# Buck_converter.net
KiCad netlist of a schematic drawn in Altium Designer
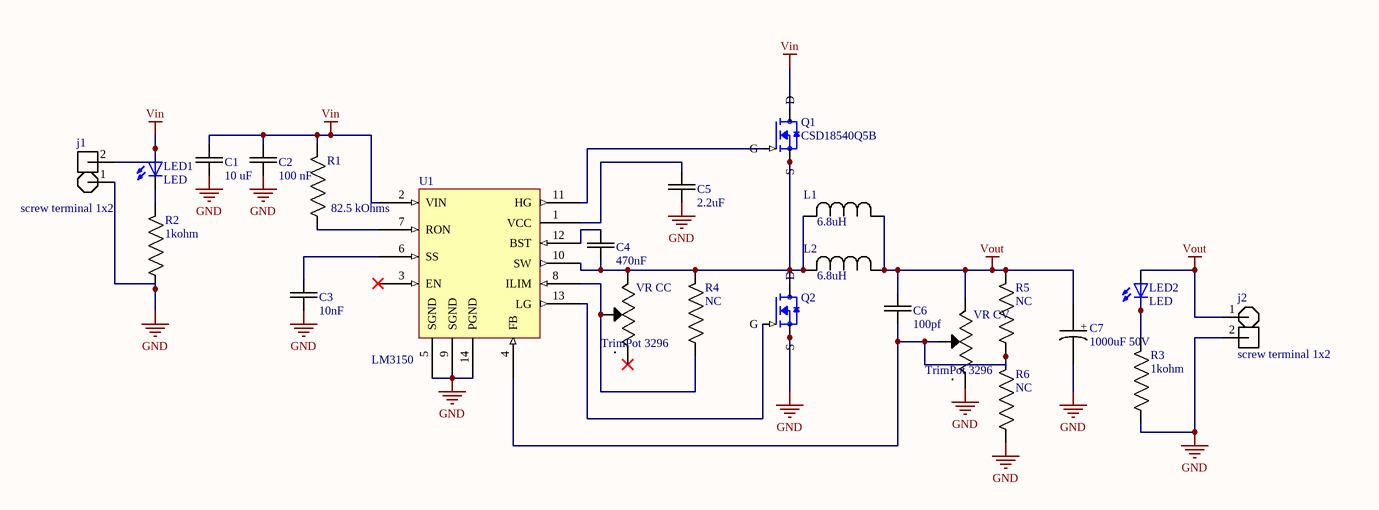
[diagram p0: Buck converter.SchDoc]

(export (version "E")
  (design (tool "Eeschema 10.0.6"))
  (components
    (comp (ref "C1")
      (value "10 uF")
      (footprint "SMD Cap 805")
      (description "0805 10 uF 50 V ±20% Tolerance X5R Multilayer Ceramic Capacitor")
      (fields
        (field (name "MANUFACTURER") "Murata")
        (field (name "MANUFACTURER PART NUMBER") "GRM21BR6YA106ME43L")
      )
      (libsource (lib "Integrated_Library") (part "Cap SMD"))
    )
    (comp (ref "C2")
      (value "100 nF")
      (footprint "SMD Cap 805")
      (fields
        (field (name "MANUFACTURER") "Kyocera AVX")
        (field (name "MANUFACTURER PART NUMBER") "08055C104KAT2A")
        (field (name "TOLERANCE") "10%")
      )
      (libsource (lib "Integrated_Library") (part "Cap SMD"))
    )
    (comp (ref "C3")
      (value "10nF")
      (footprint "SMD Cap 805")
      (description "Capacitor 10 nF 50 VDC PU=4000 ST, C0805C103K5RACTU, KEMET")
      (fields
        (field (name "MANUFACTURER") "KEMET")
        (field (name "MANUFACTURER PART NUMBER") "C0805C103K5RAC-TU")
      )
      (libsource (lib "Integrated_Library") (part "Cap SMD"))
    )
    (comp (ref "C4")
      (value "470nF")
      (footprint "SMD Cap 805")
      (fields
        (field (name "MANUFACTURER") "Taiyo Yuden")
        (field (name "MANUFACTURER PART NUMBER") "GMK212BJ474KG-T")
        (field (name "TOLERANCE") "10%")
      )
      (libsource (lib "Integrated_Library") (part "Cap SMD"))
    )
    (comp (ref "C5")
      (value "2.2uF")
      (footprint "SMD Cap 805")
      (description "CAP CER 2.2UF 35V X6S 0805")
      (fields
        (field (name "MANUFACTURER") "TDK")
        (field (name "MANUFACTURER PART NUMBER") "C2012X6S1V225K125AB")
      )
      (libsource (lib "Integrated_Library") (part "Cap SMD"))
    )
    (comp (ref "C6")
      (value "100pf")
      (footprint "SMD Cap 805")
      (fields
        (field (name "MANUFACTURER") "KEMET")
        (field (name "MANUFACTURER PART NUMBER") "C0805C101J1GACTU")
        (field (name "TOLERANCE") "5%")
      )
      (libsource (lib "Integrated_Library") (part "Cap SMD"))
    )
    (comp (ref "C7")
      (value "1000uF 50V")
      (footprint "CAP ELECTROLYTE 1000UF 50V")
      (description "CAP ALUM 1000UF 20% 50V RADIAL")
      (fields
        (field (name "MANUFACTURER") "United Chemi-Con")
        (field (name "MANUFACTURER PART NUMBER") "EKMG500ETC1R0ME11D")
      )
      (libsource (lib "Integrated_Library") (part "Cap electrolyte"))
    )
    (comp (ref "j1")
      (value "screw terminal 1x2")
      (footprint "screw terminal 1x2")
      (fields
        (field (name "MANUFACTURER") "Wurth Electronics")
        (field (name "MANUFACTURER PART NUMBER") "691214110002")
        (field (name "VOLTAGE") "300V")
      )
      (libsource (lib "connectors") (part "screw terminal 1x2"))
    )
    (comp (ref "j2")
      (value "screw terminal 1x2")
      (footprint "screw terminal 1x2")
      (fields
        (field (name "MANUFACTURER") "Wurth Electronics")
        (field (name "MANUFACTURER PART NUMBER") "691214110002")
        (field (name "VOLTAGE") "300V")
      )
      (libsource (lib "connectors") (part "screw terminal 1x2"))
    )
    (comp (ref "L1")
      (value "6.8uH")
      (footprint "Inductor DR127")
      (description "General Purpose Inductor, 6.8uH, 20%, 1 Element, Ferrite-Core, SMD, 4949")
      (fields
        (field (name "MANUFACTURER") "Eaton Cooper")
        (field (name "MANUFACTURER PART NUMBER") "DR127-470-R")
      )
      (libsource (lib "Integrated_Library") (part "Inductor CDRH127"))
    )
    (comp (ref "L2")
      (value "6.8uH")
      (footprint "Inductor DR127")
      (description "General Purpose Inductor, 6.8uH, 20%, 1 Element, Ferrite-Core, SMD, 4949")
      (fields
        (field (name "MANUFACTURER") "Eaton Cooper")
        (field (name "MANUFACTURER PART NUMBER") "DR127-470-R")
      )
      (libsource (lib "Integrated_Library") (part "Inductor CDRH127"))
    )
    (comp (ref "LED1")
      (value "LED")
      (footprint "LED3MM")
      (description "LED 3 mm (T1) red, 151031SS04000, Würth Elektronik")
      (fields
        (field (name "MANUFACTURER") "Wurth Electronics")
        (field (name "MANUFACTURER PART NUMBER") "151031SS04000")
      )
      (libsource (lib "Integrated_Library") (part "LED"))
    )
    (comp (ref "LED2")
      (value "LED")
      (footprint "LED3MM")
      (description "LED 3 mm (T1) red, 151031SS04000, Würth Elektronik")
      (fields
        (field (name "MANUFACTURER") "Wurth Electronics")
        (field (name "MANUFACTURER PART NUMBER") "151031SS04000")
      )
      (libsource (lib "Integrated_Library") (part "LED"))
    )
    (comp (ref "Q1")
      (value "CSD18540Q5B")
      (footprint "VSON-CLIP-8 - V2")
      (description "N-Channel 60V 100A _Ta_ 3.1W _Ta_, 195W _Tc_ Surface Mount 8-VSON-CLIP _5x6_")
      (fields (field (name "MF") "Texas Instruments") (field (name "DIGI-KEY_PART_NUMBER") "296-41076-1-ND"))
      (libsource (lib "Integrated_Library") (part "CSD18540Q5B"))
    )
    (comp (ref "Q2")
      (value "CSD18540Q5B")
      (footprint "VSON-CLIP-8 - V2")
      (description "N-Channel 60V 100A _Ta_ 3.1W _Ta_, 195W _Tc_ Surface Mount 8-VSON-CLIP _5x6_")
      (fields (field (name "MF") "Texas Instruments") (field (name "DIGI-KEY_PART_NUMBER") "296-41076-1-ND"))
      (libsource (lib "Integrated_Library") (part "CSD18540Q5B"))
    )
    (comp (ref "R1")
      (value "82.5 kOhms")
      (footprint "SMD Resistor 805")
      (fields
        (field (name "MANUFACTURER") "Panasonic")
        (field (name "MANUFACTURER PART NUMBER") "ERJ-6ENF8252V")
        (field (name "TOLERANCE") "1%")
      )
      (libsource (lib "Integrated_Library") (part "Resistor SMD"))
    )
    (comp (ref "R2")
      (value "1kohm")
      (footprint "SMD Resistor 805")
      (fields
        (field (name "MANUFACTURER") "Yageo")
        (field (name "MANUFACTURER PART NUMBER") "RC0805FR-071KL")
        (field (name "TOLERANCE") "1%")
      )
      (libsource (lib "Integrated_Library") (part "Resistor SMD"))
    )
    (comp (ref "R3")
      (value "1kohm")
      (footprint "SMD Resistor 805")
      (fields
        (field (name "MANUFACTURER") "Yageo")
        (field (name "MANUFACTURER PART NUMBER") "RC0805FR-071KL")
        (field (name "TOLERANCE") "1%")
      )
      (libsource (lib "Integrated_Library") (part "Resistor SMD"))
    )
    (comp (ref "R4")
      (value "NC")
      (footprint "SMD Resistor 805")
      (fields
        (field (name "MANUFACTURER") "Yageo")
        (field (name "MANUFACTURER PART NUMBER") "RC0805FR-071KL")
        (field (name "TOLERANCE") "1%")
      )
      (libsource (lib "Integrated_Library") (part "Resistor SMD"))
    )
    (comp (ref "R5")
      (value "NC")
      (footprint "SMD Resistor 805")
      (fields
        (field (name "MANUFACTURER") "Yageo")
        (field (name "MANUFACTURER PART NUMBER") "RC0805FR-071KL")
        (field (name "TOLERANCE") "1%")
      )
      (libsource (lib "Integrated_Library") (part "Resistor SMD"))
    )
    (comp (ref "R6")
      (value "NC")
      (footprint "SMD Resistor 805")
      (libsource (lib "Integrated_Library") (part "Resistor SMD"))
    )
    (comp (ref "U1")
      (value "LM3150")
      (footprint "HTSSOP (14)")
      (description "IC REG CTRLR BUCK 14TSSOP")
      (fields
        (field (name "MANUFACTURER") "TI National Semiconductor")
        (field (name "MANUFACTURER PART NUMBER") "LM3150MHX/NOPB")
      )
      (libsource (lib "Integrated_Library") (part "LM3150"))
    )
    (comp (ref "VR CC")
      (value "TrimPot 3296")
      (footprint "TrimPOT 3296W")
      (description "Trimmer Resistors - Through Hole 3/8 1Kohms Sealed Vertical Adjust")
      (fields
        (field (name "MANUFACTURER") "Bourns")
        (field (name "MANUFACTURER PART NUMBER") "3296W-1-102LF")
      )
      (libsource (lib "Integrated_Library") (part "TrimPot 3296W"))
    )
    (comp (ref "VR CV")
      (value "TrimPot 3296")
      (footprint "TrimPOT 3296W")
      (description "Trimmer Resistors - Through Hole 3/8 1Kohms Sealed Vertical Adjust")
      (fields
        (field (name "MANUFACTURER") "Bourns")
        (field (name "MANUFACTURER PART NUMBER") "3296W-1-102LF")
      )
      (libsource (lib "Integrated_Library") (part "TrimPot 3296W"))
    )
  )
  (nets
    (net (code "1") (name "GND") (class "Default")
      (node (ref "C1") (pin "1") (pintype "passive"))
      (node (ref "C2") (pin "1") (pintype "passive"))
      (node (ref "C3") (pin "1") (pintype "passive"))
      (node (ref "C5") (pin "1") (pintype "passive"))
      (node (ref "C7") (pin "N") (pinfunction "-_N") (pintype "passive"))
      (node (ref "Q2") (pin "1") (pinfunction "S_1") (pintype "power_in"))
      (node (ref "Q2") (pin "2") (pinfunction "S_2") (pintype "power_in"))
      (node (ref "Q2") (pin "3") (pinfunction "S_3") (pintype "power_in"))
      (node (ref "R2") (pin "1") (pinfunction "1_1") (pintype "passive"))
      (node (ref "R3") (pin "1") (pinfunction "1_1") (pintype "passive"))
      (node (ref "R6") (pin "1") (pinfunction "1_1") (pintype "passive"))
      (node (ref "U1") (pin "14") (pinfunction "PGND_14") (pintype "power_in"))
      (node (ref "U1") (pin "5") (pinfunction "SGND_5") (pintype "passive"))
      (node (ref "U1") (pin "9") (pinfunction "SGND_9") (pintype "passive"))
      (node (ref "VR CV") (pin "1") (pinfunction "CCW_1") (pintype "passive"))
      (node (ref "j1") (pin "1") (pinfunction "1_1") (pintype "passive"))
      (node (ref "j2") (pin "2") (pinfunction "2_2") (pintype "passive"))
    )
    (net (code "2") (name "Net-(LED1-PadC)") (class "Default")
      (node (ref "LED1") (pin "C") (pinfunction "C_C") (pintype "passive"))
      (node (ref "R2") (pin "2") (pinfunction "2_2") (pintype "passive"))
    )
    (net (code "3") (name "Net-(LED2-PadC)") (class "Default")
      (node (ref "LED2") (pin "C") (pinfunction "C_C") (pintype "passive"))
      (node (ref "R3") (pin "2") (pinfunction "2_2") (pintype "passive"))
    )
    (net (code "4") (name "Net-(Q1-G)") (class "Default")
      (node (ref "Q1") (pin "4") (pinfunction "G_4") (pintype "input"))
      (node (ref "U1") (pin "11") (pinfunction "HG_11") (pintype "output"))
    )
    (net (code "5") (name "Net-(Q2-D)") (class "Default")
      (node (ref "C4") (pin "1") (pintype "passive"))
      (node (ref "L1") (pin "2") (pinfunction "2_2") (pintype "passive"))
      (node (ref "L2") (pin "2") (pinfunction "2_2") (pintype "passive"))
      (node (ref "Q1") (pin "1") (pinfunction "S_1") (pintype "power_in"))
      (node (ref "Q1") (pin "2") (pinfunction "S_2") (pintype "power_in"))
      (node (ref "Q1") (pin "3") (pinfunction "S_3") (pintype "power_in"))
      (node (ref "Q2") (pin "5") (pinfunction "D_5") (pintype "power_in"))
      (node (ref "R4") (pin "2") (pinfunction "2_2") (pintype "passive"))
      (node (ref "U1") (pin "10") (pinfunction "SW_10") (pintype "output"))
      (node (ref "VR CC") (pin "3") (pinfunction "CW_3") (pintype "passive"))
    )
    (net (code "6") (name "Net-(Q2-G)") (class "Default")
      (node (ref "Q2") (pin "4") (pinfunction "G_4") (pintype "input"))
      (node (ref "U1") (pin "13") (pinfunction "LG_13") (pintype "output"))
    )
    (net (code "7") (name "Net-(U1-BST)") (class "Default")
      (node (ref "C4") (pin "2") (pintype "passive"))
      (node (ref "U1") (pin "12") (pinfunction "BST_12") (pintype "input"))
    )
    (net (code "8") (name "Net-(U1-FB)") (class "Default")
      (node (ref "C6") (pin "1") (pintype "passive"))
      (node (ref "R5") (pin "1") (pinfunction "1_1") (pintype "passive"))
      (node (ref "R6") (pin "2") (pinfunction "2_2") (pintype "passive"))
      (node (ref "U1") (pin "4") (pinfunction "FB_4") (pintype "input"))
      (node (ref "VR CV") (pin "2") (pinfunction "WIPER_2") (pintype "passive"))
    )
    (net (code "9") (name "Net-(U1-ILIM)") (class "Default")
      (node (ref "R4") (pin "1") (pinfunction "1_1") (pintype "passive"))
      (node (ref "U1") (pin "8") (pinfunction "ILIM_8") (pintype "input"))
      (node (ref "VR CC") (pin "2") (pinfunction "WIPER_2") (pintype "passive"))
    )
    (net (code "10") (name "Net-(U1-RON)") (class "Default")
      (node (ref "R1") (pin "1") (pinfunction "1_1") (pintype "passive"))
      (node (ref "U1") (pin "7") (pinfunction "RON_7") (pintype "input"))
    )
    (net (code "11") (name "Net-(U1-SS)") (class "Default")
      (node (ref "C3") (pin "2") (pintype "passive"))
      (node (ref "U1") (pin "6") (pinfunction "SS_6") (pintype "input"))
    )
    (net (code "12") (name "Net-(U1-VCC)") (class "Default")
      (node (ref "C5") (pin "2") (pintype "passive"))
      (node (ref "U1") (pin "1") (pinfunction "VCC_1") (pintype "power_in"))
    )
    (net (code "13") (name "Vin") (class "Default")
      (node (ref "C1") (pin "2") (pintype "passive"))
      (node (ref "C2") (pin "2") (pintype "passive"))
      (node (ref "LED1") (pin "A") (pinfunction "A_A") (pintype "passive"))
      (node (ref "Q1") (pin "5") (pinfunction "D_5") (pintype "power_in"))
      (node (ref "R1") (pin "2") (pinfunction "2_2") (pintype "passive"))
      (node (ref "U1") (pin "2") (pinfunction "VIN_2") (pintype "input"))
      (node (ref "j1") (pin "2") (pinfunction "2_2") (pintype "passive"))
    )
    (net (code "14") (name "Vout") (class "Default")
      (node (ref "C6") (pin "2") (pintype "passive"))
      (node (ref "C7") (pin "P") (pinfunction "+_P") (pintype "passive"))
      (node (ref "L1") (pin "1") (pinfunction "1_1") (pintype "passive"))
      (node (ref "L2") (pin "1") (pinfunction "1_1") (pintype "passive"))
      (node (ref "LED2") (pin "A") (pinfunction "A_A") (pintype "passive"))
      (node (ref "R5") (pin "2") (pinfunction "2_2") (pintype "passive"))
      (node (ref "VR CV") (pin "3") (pinfunction "CW_3") (pintype "passive"))
      (node (ref "j2") (pin "1") (pinfunction "1_1") (pintype "passive"))
    )
    (net (code "15") (name "unconnected-(U1-EN-Pad3)") (class "Default")
      (node (ref "U1") (pin "3") (pinfunction "EN_3") (pintype "input+no_connect"))
    )
    (net (code "16") (name "unconnected-(VR CC-CCW-Pad1)") (class "Default")
      (node (ref "VR CC") (pin "1") (pinfunction "CCW_1") (pintype "passive+no_connect"))
    )
  )
)
